# SH11_-_RS-485.net
KiCad netlist of a schematic drawn in Altium Designer
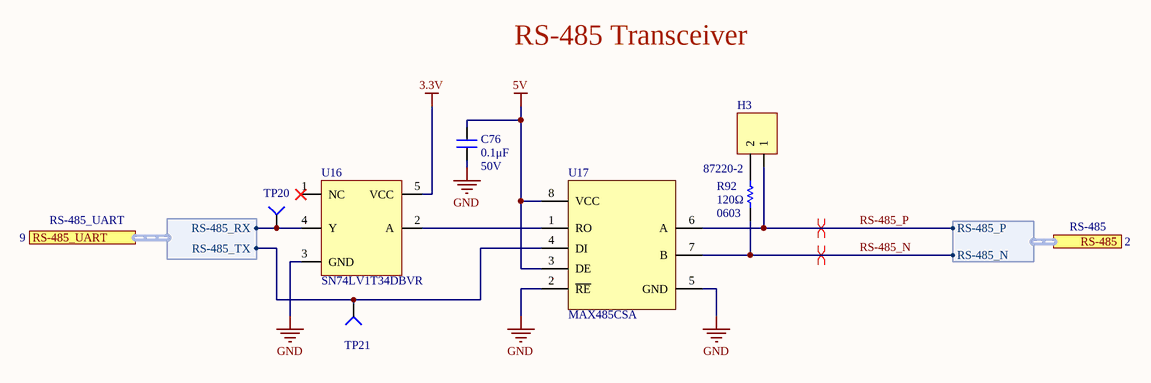
[diagram p0: SH11 - RS-485.SchDoc]

(export (version "E")
  (design (tool "Eeschema 10.0.6"))
  (components
    (comp (ref "C76")
      (value "0.1μF")
      (footprint "CAP0603")
      (description "CAP CER 0.1UF 50V X7R 0603")
      (fields (field (name "VOLTAGE RATING") "50V") (field (name "Comment") "CAP_0.1uF_50V_0603"))
      (libsource (lib "UWRT_Schematic_Library_2020") (part "CAP_0.1uF_50V_0603"))
    )
    (comp (ref "H3")
      (value "JUMPER_2")
      (footprint "HDR1X2")
      (description "HEADER 2X1")
      (fields (field (name "MANUFACTURER PART NUMBER 1") "87220-2"))
      (libsource (lib "UWRT_Schematic_Library_2020") (part "JUMPER_2"))
    )
    (comp (ref "R92")
      (value "120Ω")
      (footprint "RESC0603(1608)_N")
      (description "RES 120 OHM 5% 1/10W 0603")
      (fields
        (field (name "TOLERANCE") "5%")
        (field (name "CASE CODE (IMPERIAL)") "0603")
        (field (name "Comment") "RES_120Ω_0603")
      )
      (libsource (lib "UWRT_Schematic_Library_2020") (part "RES_120Ω_0603_5%"))
    )
    (comp (ref "TP20")
      (value "TESTPOINT_SMD_LOOP")
      (footprint "S1751-46R")
      (description "PC TEST POINT SMD")
      (libsource (lib "UWRT_Schematic_Library_2020") (part "TESTPOINT_SMD_LOOP"))
    )
    (comp (ref "TP21")
      (value "TESTPOINT_SMD_LOOP")
      (footprint "S1751-46R")
      (description "PC TEST POINT SMD")
      (libsource (lib "UWRT_Schematic_Library_2020") (part "TESTPOINT_SMD_LOOP"))
    )
    (comp (ref "U16")
      (value "SN74LV1T34")
      (footprint "SN74LV1T34DBVR")
      (description "Bus Driver, LV/LV-A/LVX/H Series, 1-Func, 1-Bit, True Output, CMOS, PDSO5")
      (fields (field (name "MANUFACTURER PART NUMBER 1") "SN74LV1T34DBVR"))
      (libsource (lib "UWRT_Schematic_Library_2020") (part "SN74LV1T34"))
    )
    (comp (ref "U17")
      (value "MAX485CSA")
      (footprint "SOIC127P600X175-8N")
      (description "1/1 Transceiver Half RS422, RS485 8-SOIC")
      (libsource (lib "UWRT_Schematic_Library_2020") (part "MAX485CSA"))
    )
  )
  (nets
    (net (code "3") (name "/RS-485_N") (class "Default")
      (node (ref "R92") (pin "1") (pinfunction "1_1") (pintype "passive"))
      (node (ref "U17") (pin "7") (pinfunction "B_7") (pintype "passive"))
    )
    (net (code "4") (name "/RS-485_P") (class "Default")
      (node (ref "H3") (pin "1") (pinfunction "1_1") (pintype "passive"))
      (node (ref "U17") (pin "6") (pinfunction "A_6") (pintype "passive"))
    )
    (net (code "7") (name "3.3V") (class "Default")
      (node (ref "U16") (pin "5") (pinfunction "VCC_5") (pintype "passive"))
    )
    (net (code "8") (name "5V") (class "Default")
      (node (ref "C76") (pin "1") (pinfunction "1_1") (pintype "passive"))
      (node (ref "U17") (pin "3") (pinfunction "DE_3") (pintype "passive"))
      (node (ref "U17") (pin "8") (pinfunction "VCC_8") (pintype "power_in"))
    )
    (net (code "9") (name "GND") (class "Default")
      (node (ref "C76") (pin "2") (pinfunction "2_2") (pintype "passive"))
      (node (ref "U16") (pin "3") (pinfunction "GND_3") (pintype "passive"))
      (node (ref "U17") (pin "2") (pinfunction "~{RE}_2") (pintype "passive"))
      (node (ref "U17") (pin "5") (pinfunction "GND_5") (pintype "power_in"))
    )
    (net (code "10") (name "Net-(H3-Pad2)") (class "Default")
      (node (ref "H3") (pin "2") (pinfunction "2_2") (pintype "passive"))
      (node (ref "R92") (pin "2") (pinfunction "2_2") (pintype "passive"))
    )
    (net (code "11") (name "Net-(TP20-=value)") (class "Default")
      (node (ref "TP20") (pin "1") (pinfunction "=value_1") (pintype "passive"))
      (node (ref "U16") (pin "4") (pinfunction "Y_4") (pintype "passive"))
    )
    (net (code "12") (name "Net-(TP21-=value)") (class "Default")
      (node (ref "TP21") (pin "1") (pinfunction "=value_1") (pintype "passive"))
      (node (ref "U17") (pin "4") (pinfunction "DI_4") (pintype "passive"))
    )
    (net (code "13") (name "Net-(U16-A)") (class "Default")
      (node (ref "U16") (pin "2") (pinfunction "A_2") (pintype "passive"))
      (node (ref "U17") (pin "1") (pinfunction "RO_1") (pintype "passive"))
    )
    (net (code "14") (name "unconnected-(U16-NC-Pad1)") (class "Default")
      (node (ref "U16") (pin "1") (pinfunction "NC_1") (pintype "passive+no_connect"))
    )
  )
)
